# untitled.net
KiCad netlist of a schematic drawn in EAGLE
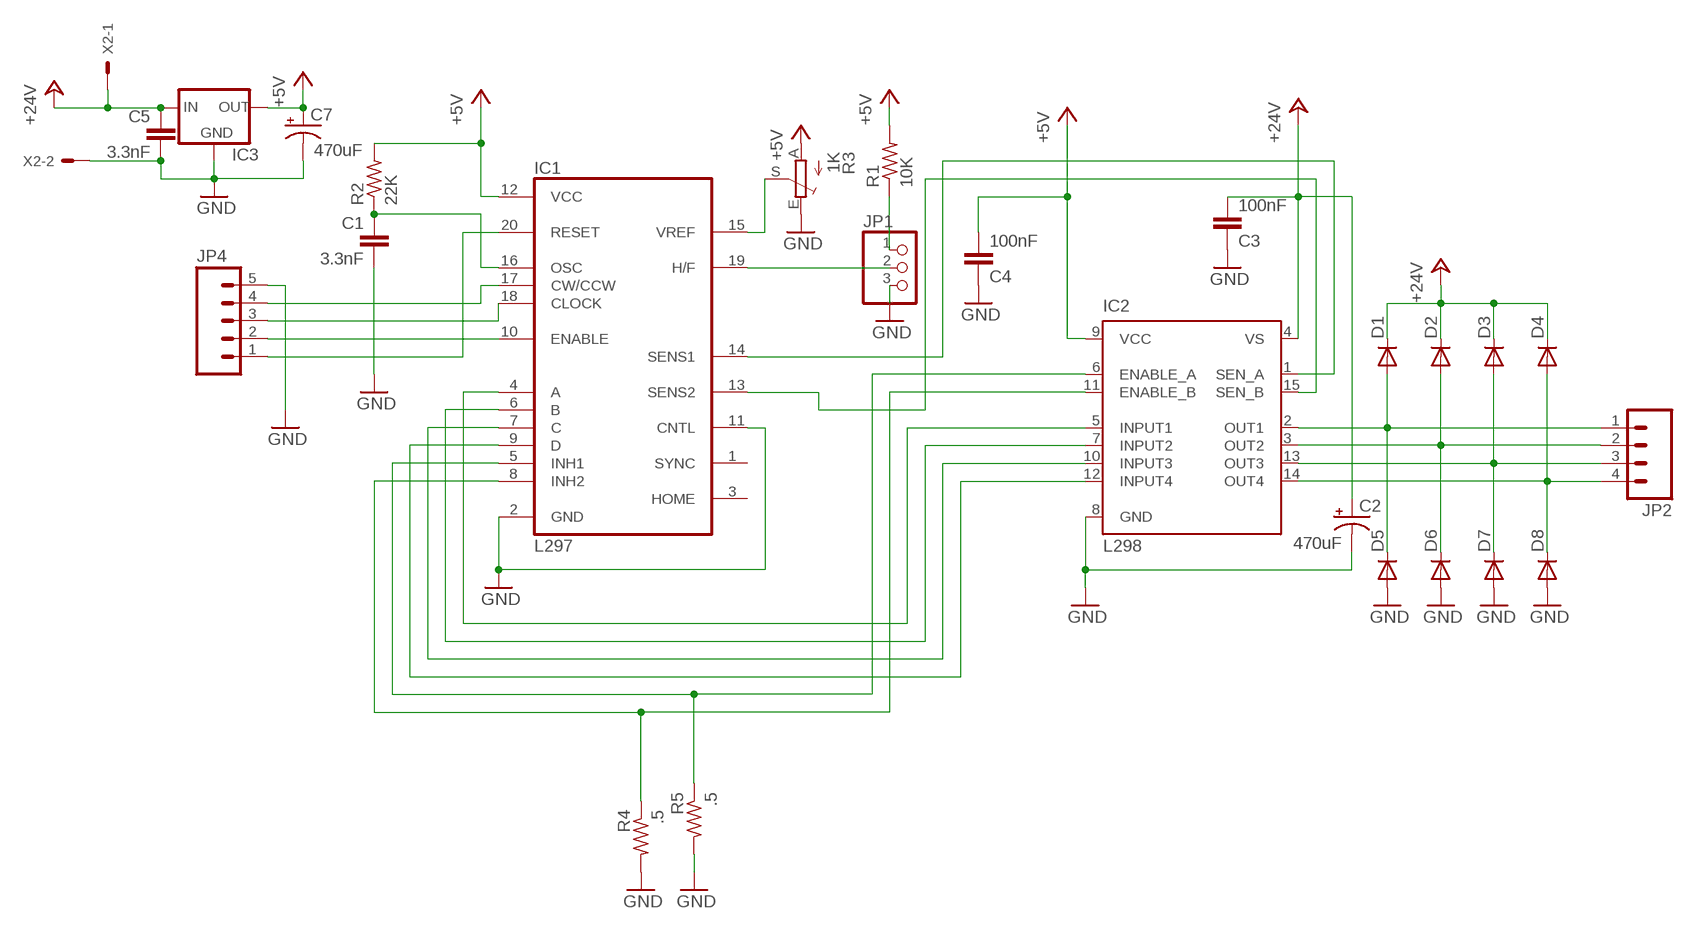
[diagram p0: schematic, sheet 1]

(export (version "E")
  (design (tool "Eeschema 10.0.6"))
  (components
    (comp (ref "C1")
      (value "3.3nF")
      (footprint "eagle-import:C2.5-3")
      (libsource (lib "eagle-import") (part "C2,5-3"))
    )
    (comp (ref "C2")
      (value "470uF")
      (footprint "eagle-import:CPOL-RADIAL-100UF-25V")
      (libsource (lib "eagle-import") (part "CAP_POLPTH1"))
    )
    (comp (ref "C3")
      (value "100nF")
      (footprint "eagle-import:C2.5-3")
      (libsource (lib "eagle-import") (part "C2,5-3"))
    )
    (comp (ref "C4")
      (value "100nF")
      (footprint "eagle-import:C2.5-3")
      (libsource (lib "eagle-import") (part "C2,5-3"))
    )
    (comp (ref "C5")
      (value "3.3nF")
      (footprint "eagle-import:C2.5-3")
      (libsource (lib "eagle-import") (part "C2,5-3"))
    )
    (comp (ref "C7")
      (value "470uF")
      (footprint "eagle-import:CPOL-RADIAL-100UF-25V")
      (libsource (lib "eagle-import") (part "CAP_POLPTH1"))
    )
    (comp (ref "D1")
      (value "DIODE-DO201-15")
      (footprint "eagle-import:DO201-15")
      (libsource (lib "eagle-import") (part "DIODE-DO201-15"))
    )
    (comp (ref "D2")
      (value "DIODE-DO201-15")
      (footprint "eagle-import:DO201-15")
      (libsource (lib "eagle-import") (part "DIODE-DO201-15"))
    )
    (comp (ref "D3")
      (value "DIODE-DO201-15")
      (footprint "eagle-import:DO201-15")
      (libsource (lib "eagle-import") (part "DIODE-DO201-15"))
    )
    (comp (ref "D4")
      (value "DIODE-DO201-15")
      (footprint "eagle-import:DO201-15")
      (libsource (lib "eagle-import") (part "DIODE-DO201-15"))
    )
    (comp (ref "D5")
      (value "DIODE-DO201-15")
      (footprint "eagle-import:DO201-15")
      (libsource (lib "eagle-import") (part "DIODE-DO201-15"))
    )
    (comp (ref "D6")
      (value "DIODE-DO201-15")
      (footprint "eagle-import:DO201-15")
      (libsource (lib "eagle-import") (part "DIODE-DO201-15"))
    )
    (comp (ref "D7")
      (value "DIODE-DO201-15")
      (footprint "eagle-import:DO201-15")
      (libsource (lib "eagle-import") (part "DIODE-DO201-15"))
    )
    (comp (ref "D8")
      (value "DIODE-DO201-15")
      (footprint "eagle-import:DO201-15")
      (libsource (lib "eagle-import") (part "DIODE-DO201-15"))
    )
    (comp (ref "IC1")
      (value "L297")
      (footprint "eagle-import:DIL20")
      (fields (field (name "MPN") "L297/1"))
      (libsource (lib "eagle-import") (part "L297"))
    )
    (comp (ref "IC2")
      (value "L298")
      (footprint "eagle-import:MULTIWATT-15")
      (fields (field (name "MPN") "L298N"))
      (libsource (lib "eagle-import") (part "L298"))
    )
    (comp (ref "IC3")
      (value "V_REG_78XXSINK")
      (footprint "eagle-import:TO220-IGO")
      (libsource (lib "eagle-import") (part "V_REG_78XXSINK"))
    )
    (comp (ref "JP1")
      (value "PINHD-1X3")
      (footprint "eagle-import:1X03")
      (libsource (lib "eagle-import") (part "PINHD-1X3"))
    )
    (comp (ref "JP2")
      (value "M04PTH")
      (footprint "eagle-import:1X04")
      (libsource (lib "eagle-import") (part "M04PTH"))
    )
    (comp (ref "JP4")
      (value "M05PTH")
      (footprint "eagle-import:1X05")
      (libsource (lib "eagle-import") (part "M05PTH"))
    )
    (comp (ref "R1")
      (value "10K")
      (footprint "eagle-import:0207_10")
      (libsource (lib "eagle-import") (part "R-US_0207/10"))
    )
    (comp (ref "R2")
      (value "22K")
      (footprint "eagle-import:0207_10")
      (libsource (lib "eagle-import") (part "R-US_0207/10"))
    )
    (comp (ref "R3")
      (value "1K")
      (footprint "eagle-import:B64Y")
      (libsource (lib "eagle-import") (part "TRIM_EU-B64Y"))
    )
    (comp (ref "R4")
      (value ".5")
      (footprint "eagle-import:0617_22")
      (libsource (lib "eagle-import") (part "R-US_0617/22"))
    )
    (comp (ref "R5")
      (value ".5")
      (footprint "eagle-import:0617_22")
      (libsource (lib "eagle-import") (part "R-US_0617/22"))
    )
    (comp (ref "X2")
      (value "KK-156-2")
      (footprint "eagle-import:KK-156-2")
      (libsource (lib "eagle-import") (part "KK-156-2"))
    )
  )
  (nets
    (net (code "1") (name "+5V") (class "Default")
      (node (ref "C4") (pin "2") (pinfunction "2_2") (pintype "passive"))
      (node (ref "C7") (pin "1") (pinfunction "+_1") (pintype "passive"))
      (node (ref "IC1") (pin "12") (pinfunction "VCC_12") (pintype "power_in"))
      (node (ref "IC2") (pin "9") (pinfunction "VCC_9") (pintype "power_in"))
      (node (ref "IC3") (pin "OUT") (pinfunction "OUT_OUT") (pintype "output"))
      (node (ref "R1") (pin "2") (pinfunction "2_2") (pintype "passive"))
      (node (ref "R2") (pin "2") (pinfunction "2_2") (pintype "passive"))
      (node (ref "R3") (pin "A") (pinfunction "A_A") (pintype "passive"))
    )
    (net (code "2") (name "+24V") (class "Default")
      (node (ref "C2") (pin "1") (pinfunction "+_1") (pintype "passive"))
      (node (ref "C3") (pin "2") (pinfunction "2_2") (pintype "passive"))
      (node (ref "C5") (pin "1") (pinfunction "1_1") (pintype "passive"))
      (node (ref "D1") (pin "C") (pinfunction "C_C") (pintype "passive"))
      (node (ref "D2") (pin "C") (pinfunction "C_C") (pintype "passive"))
      (node (ref "D3") (pin "C") (pinfunction "C_C") (pintype "passive"))
      (node (ref "D4") (pin "C") (pinfunction "C_C") (pintype "passive"))
      (node (ref "IC2") (pin "4") (pinfunction "VS_4") (pintype "power_in"))
      (node (ref "IC3") (pin "IN") (pinfunction "IN_IN") (pintype "input"))
      (node (ref "X2") (pin "1") (pinfunction "S_1") (pintype "passive"))
    )
    (net (code "3") (name "GND") (class "Default")
      (node (ref "C1") (pin "2") (pinfunction "2_2") (pintype "passive"))
      (node (ref "C2") (pin "2") (pinfunction "-_2") (pintype "passive"))
      (node (ref "C3") (pin "1") (pinfunction "1_1") (pintype "passive"))
      (node (ref "C4") (pin "1") (pinfunction "1_1") (pintype "passive"))
      (node (ref "C5") (pin "2") (pinfunction "2_2") (pintype "passive"))
      (node (ref "C7") (pin "2") (pinfunction "-_2") (pintype "passive"))
      (node (ref "D5") (pin "A") (pinfunction "A_A") (pintype "passive"))
      (node (ref "D6") (pin "A") (pinfunction "A_A") (pintype "passive"))
      (node (ref "D7") (pin "A") (pinfunction "A_A") (pintype "passive"))
      (node (ref "D8") (pin "A") (pinfunction "A_A") (pintype "passive"))
      (node (ref "IC1") (pin "11") (pinfunction "CNTL_11") (pintype "input"))
      (node (ref "IC1") (pin "2") (pinfunction "GND_2") (pintype "power_in"))
      (node (ref "IC2") (pin "8") (pinfunction "GND_8") (pintype "power_in"))
      (node (ref "IC3") (pin "GND") (pinfunction "GND_GND") (pintype "input"))
      (node (ref "JP1") (pin "3") (pinfunction "3_3") (pintype "passive"))
      (node (ref "JP4") (pin "5") (pinfunction "5_5") (pintype "passive"))
      (node (ref "R3") (pin "E") (pinfunction "E_E") (pintype "passive"))
      (node (ref "R4") (pin "2") (pinfunction "2_2") (pintype "passive"))
      (node (ref "R5") (pin "2") (pinfunction "2_2") (pintype "passive"))
      (node (ref "X2") (pin "2") (pinfunction "S_2") (pintype "passive"))
    )
    (net (code "4") (name "Net-(IC1-A)") (class "Default")
      (node (ref "IC1") (pin "4") (pinfunction "A_4") (pintype "output"))
      (node (ref "IC2") (pin "5") (pinfunction "INPUT1_5") (pintype "input"))
    )
    (net (code "5") (name "Net-(IC1-B)") (class "Default")
      (node (ref "IC1") (pin "6") (pinfunction "B_6") (pintype "output"))
      (node (ref "IC2") (pin "7") (pinfunction "INPUT2_7") (pintype "input"))
    )
    (net (code "6") (name "Net-(IC1-C)") (class "Default")
      (node (ref "IC1") (pin "7") (pinfunction "C_7") (pintype "output"))
      (node (ref "IC2") (pin "10") (pinfunction "INPUT3_10") (pintype "input"))
    )
    (net (code "7") (name "Net-(IC1-CLOCK)") (class "Default")
      (node (ref "IC1") (pin "18") (pinfunction "CLOCK_18") (pintype "input"))
      (node (ref "JP4") (pin "3") (pinfunction "3_3") (pintype "passive"))
    )
    (net (code "8") (name "Net-(IC1-CW{slash}CCW)") (class "Default")
      (node (ref "IC1") (pin "17") (pinfunction "CW/CCW_17") (pintype "input"))
      (node (ref "JP4") (pin "4") (pinfunction "4_4") (pintype "passive"))
    )
    (net (code "9") (name "Net-(IC1-D)") (class "Default")
      (node (ref "IC1") (pin "9") (pinfunction "D_9") (pintype "output"))
      (node (ref "IC2") (pin "12") (pinfunction "INPUT4_12") (pintype "input"))
    )
    (net (code "10") (name "Net-(IC1-ENABLE)") (class "Default")
      (node (ref "IC1") (pin "10") (pinfunction "ENABLE_10") (pintype "input"))
      (node (ref "JP4") (pin "2") (pinfunction "2_2") (pintype "passive"))
    )
    (net (code "11") (name "Net-(IC1-H{slash}F)") (class "Default")
      (node (ref "IC1") (pin "19") (pinfunction "H/F_19") (pintype "input"))
      (node (ref "JP1") (pin "2") (pinfunction "2_2") (pintype "passive"))
    )
    (net (code "12") (name "Net-(IC1-INH1)") (class "Default")
      (node (ref "IC1") (pin "5") (pinfunction "INH1_5") (pintype "output"))
      (node (ref "IC2") (pin "6") (pinfunction "ENABLE_A_6") (pintype "input"))
      (node (ref "R5") (pin "1") (pinfunction "1_1") (pintype "passive"))
    )
    (net (code "13") (name "Net-(IC1-INH2)") (class "Default")
      (node (ref "IC1") (pin "8") (pinfunction "INH2_8") (pintype "output"))
      (node (ref "IC2") (pin "11") (pinfunction "ENABLE_B_11") (pintype "input"))
      (node (ref "R4") (pin "1") (pinfunction "1_1") (pintype "passive"))
    )
    (net (code "14") (name "Net-(IC1-OSC)") (class "Default")
      (node (ref "C1") (pin "1") (pinfunction "1_1") (pintype "passive"))
      (node (ref "IC1") (pin "16") (pinfunction "OSC_16") (pintype "bidirectional"))
      (node (ref "R2") (pin "1") (pinfunction "1_1") (pintype "passive"))
    )
    (net (code "15") (name "Net-(IC1-RESET)") (class "Default")
      (node (ref "IC1") (pin "20") (pinfunction "RESET_20") (pintype "input"))
      (node (ref "JP4") (pin "1") (pinfunction "1_1") (pintype "passive"))
    )
    (net (code "16") (name "Net-(IC1-SENS1)") (class "Default")
      (node (ref "IC1") (pin "14") (pinfunction "SENS1_14") (pintype "output"))
      (node (ref "IC2") (pin "1") (pinfunction "SEN_A_1") (pintype "input"))
    )
    (net (code "17") (name "Net-(IC1-SENS2)") (class "Default")
      (node (ref "IC1") (pin "13") (pinfunction "SENS2_13") (pintype "output"))
      (node (ref "IC2") (pin "15") (pinfunction "SEN_B_15") (pintype "input"))
    )
    (net (code "18") (name "Net-(IC1-VREF)") (class "Default")
      (node (ref "IC1") (pin "15") (pinfunction "VREF_15") (pintype "input"))
      (node (ref "R3") (pin "S") (pinfunction "S_S") (pintype "passive"))
    )
    (net (code "19") (name "Net-(IC2-OUT1)") (class "Default")
      (node (ref "D1") (pin "A") (pinfunction "A_A") (pintype "passive"))
      (node (ref "D5") (pin "C") (pinfunction "C_C") (pintype "passive"))
      (node (ref "IC2") (pin "2") (pinfunction "OUT1_2") (pintype "output"))
      (node (ref "JP2") (pin "1") (pinfunction "1_1") (pintype "passive"))
    )
    (net (code "20") (name "Net-(IC2-OUT2)") (class "Default")
      (node (ref "D2") (pin "A") (pinfunction "A_A") (pintype "passive"))
      (node (ref "D6") (pin "C") (pinfunction "C_C") (pintype "passive"))
      (node (ref "IC2") (pin "3") (pinfunction "OUT2_3") (pintype "output"))
      (node (ref "JP2") (pin "2") (pinfunction "2_2") (pintype "passive"))
    )
    (net (code "21") (name "Net-(IC2-OUT3)") (class "Default")
      (node (ref "D3") (pin "A") (pinfunction "A_A") (pintype "passive"))
      (node (ref "D7") (pin "C") (pinfunction "C_C") (pintype "passive"))
      (node (ref "IC2") (pin "13") (pinfunction "OUT3_13") (pintype "output"))
      (node (ref "JP2") (pin "3") (pinfunction "3_3") (pintype "passive"))
    )
    (net (code "22") (name "Net-(IC2-OUT4)") (class "Default")
      (node (ref "D4") (pin "A") (pinfunction "A_A") (pintype "passive"))
      (node (ref "D8") (pin "C") (pinfunction "C_C") (pintype "passive"))
      (node (ref "IC2") (pin "14") (pinfunction "OUT4_14") (pintype "output"))
      (node (ref "JP2") (pin "4") (pinfunction "4_4") (pintype "passive"))
    )
    (net (code "23") (name "Net-(JP1-Pad1)") (class "Default")
      (node (ref "JP1") (pin "1") (pinfunction "1_1") (pintype "passive"))
      (node (ref "R1") (pin "1") (pinfunction "1_1") (pintype "passive"))
    )
    (net (code "24") (name "unconnected-(IC1-HOME-Pad3)") (class "Default")
      (node (ref "IC1") (pin "3") (pinfunction "HOME_3") (pintype "output"))
    )
    (net (code "25") (name "unconnected-(IC1-SYNC-Pad1)") (class "Default")
      (node (ref "IC1") (pin "1") (pinfunction "SYNC_1") (pintype "output"))
    )
  )
)
